# Power-Switch-Board-v1.net
KiCad netlist of a schematic drawn in EAGLE
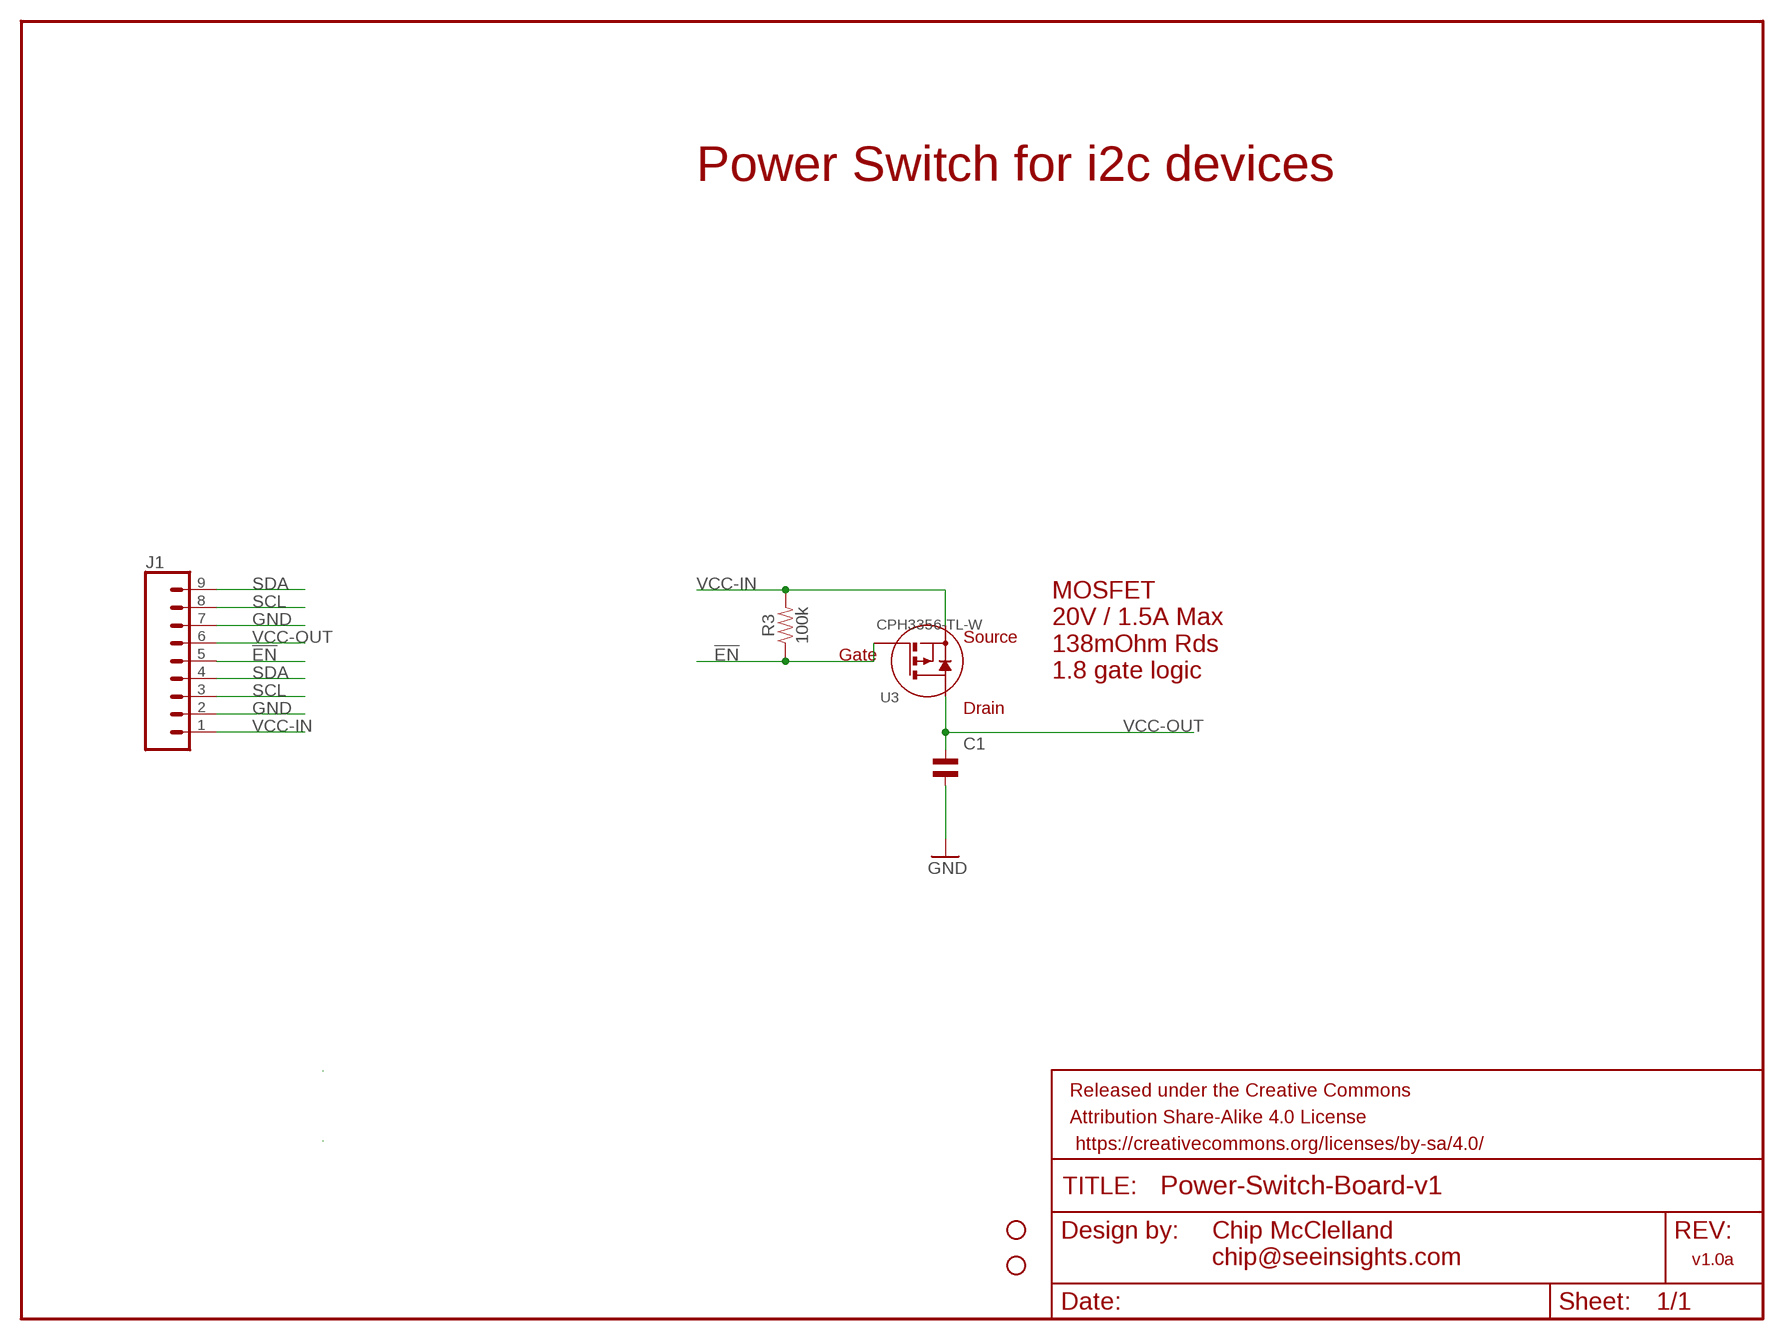
[diagram p0: schematic, sheet 1]

(export (version "E")
  (design (tool "Eeschema 10.0.6"))
  (components
    (comp (ref "C1")
      (value "CAP-MF-0.1UF-")
      (footprint "eagle-import:C0805")
      (fields
        (field (name "HOUSEPART") "YES")
        (field (name "MPN") "MF-CAP-0805-0.1uF")
        (field (name "VOLTAGE") "50V")
      )
      (libsource (lib "eagle-import") (part "CAP-MF-0.1UF-"))
    )
    (comp (ref "FRAME1")
      (value "FRAME-LETTER")
      (footprint "eagle-import:CREATIVE_COMMONS")
      (libsource (lib "eagle-import") (part "FRAME-LETTER"))
    )
    (comp (ref "H1")
      (value "STAND-OFF-M2.5")
      (footprint "eagle-import:STAND-OFF-M2.5")
      (libsource (lib "eagle-import") (part "STAND-OFF-M2.5"))
    )
    (comp (ref "H2")
      (value "STAND-OFF-M2.5")
      (footprint "eagle-import:STAND-OFF-M2.5")
      (libsource (lib "eagle-import") (part "STAND-OFF-M2.5"))
    )
    (comp (ref "J1")
      (value "CONN_09")
      (footprint "eagle-import:1X09")
      (libsource (lib "eagle-import") (part "CONN_09"))
    )
    (comp (ref "R3")
      (value "100k")
      (footprint "eagle-import:0805")
      (fields (field (name "MPN") "MF-RES-0805-100K"))
      (libsource (lib "eagle-import") (part "RESISTOR-MF-100K-0805"))
    )
    (comp (ref "U3")
      (value "CPH3356-TL-W")
      (footprint "eagle-import:SOT-23_ONS")
      (fields (field (name "COPYRIGHT") "Copyright (C) 2021 Ultra Librarian. All rights reserved."))
      (libsource (lib "eagle-import") (part "CPH3356-TL-W"))
    )
  )
  (nets
    (net (code "1") (name "/SCL") (class "Default")
      (node (ref "J1") (pin "3") (pinfunction "3_3") (pintype "passive"))
      (node (ref "J1") (pin "8") (pinfunction "8_8") (pintype "passive"))
    )
    (net (code "2") (name "/SDA") (class "Default")
      (node (ref "J1") (pin "4") (pinfunction "4_4") (pintype "passive"))
      (node (ref "J1") (pin "9") (pinfunction "9_9") (pintype "passive"))
    )
    (net (code "3") (name "/VCC-IN") (class "Default")
      (node (ref "J1") (pin "1") (pinfunction "1_1") (pintype "passive"))
      (node (ref "R3") (pin "2") (pinfunction "2_2") (pintype "passive"))
      (node (ref "U3") (pin "2") (pinfunction "SOURCE_2") (pintype "passive"))
    )
    (net (code "4") (name "/VCC-OUT") (class "Default")
      (node (ref "C1") (pin "P$1") (pinfunction "P$1_P$1") (pintype "passive"))
      (node (ref "J1") (pin "6") (pinfunction "6_6") (pintype "passive"))
      (node (ref "U3") (pin "3") (pinfunction "DRAIN_3") (pintype "passive"))
    )
    (net (code "5") (name "/~{EN}") (class "Default")
      (node (ref "J1") (pin "5") (pinfunction "5_5") (pintype "passive"))
      (node (ref "R3") (pin "1") (pinfunction "1_1") (pintype "passive"))
      (node (ref "U3") (pin "1") (pinfunction "GATE_1") (pintype "passive"))
    )
    (net (code "6") (name "GND") (class "Default")
      (node (ref "C1") (pin "P$2") (pinfunction "P$2_P$2") (pintype "passive"))
      (node (ref "J1") (pin "2") (pinfunction "2_2") (pintype "passive"))
      (node (ref "J1") (pin "7") (pinfunction "7_7") (pintype "passive"))
    )
  )
)
